# Schemetic.net
KiCad netlist of a schematic drawn in Altium Designer
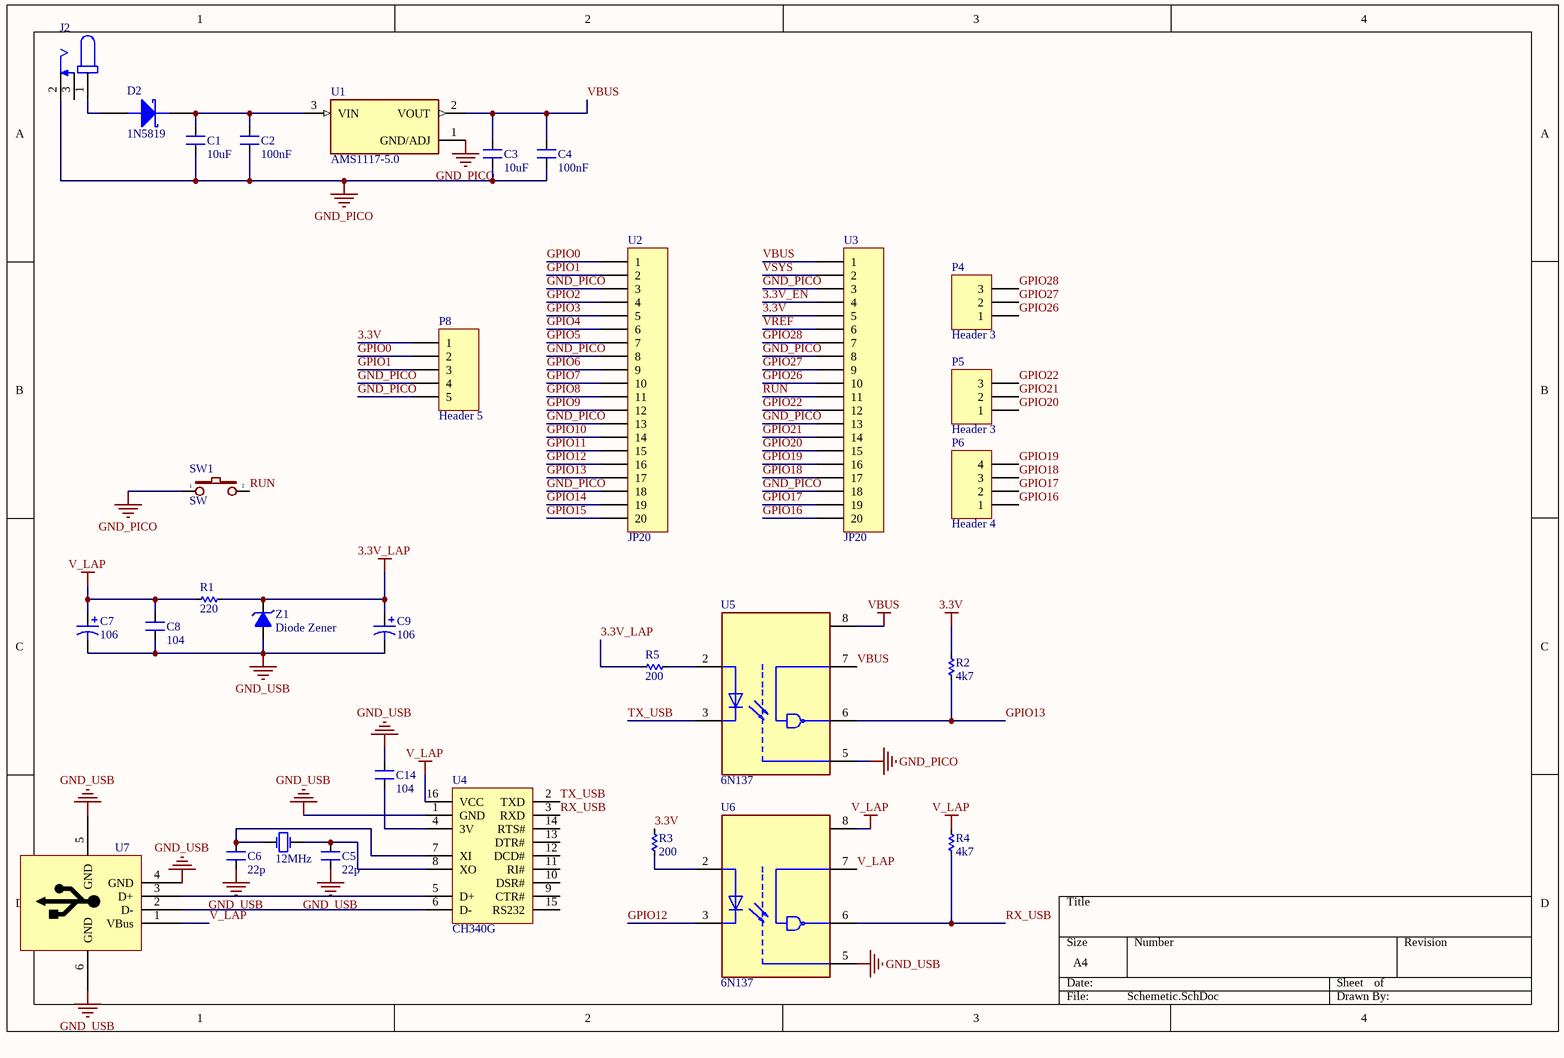
[diagram p0: Schemetic.SchDoc]

(export (version "E")
  (design (tool "Eeschema 10.0.6"))
  (components
    (comp (ref "C1")
      (value "10uF")
      (footprint "CN2")
      (description "Cap np 104 => 105pF")
      (libsource (lib "Altium Library") (part "CN2"))
    )
    (comp (ref "C2")
      (value "100nF")
      (footprint "CN2")
      (description "Cap np 104 => 105pF")
      (libsource (lib "syhaunguyen") (part "CN2"))
    )
    (comp (ref "C3")
      (value "10uF")
      (footprint "CN2")
      (description "Cap np 104 => 105pF")
      (libsource (lib "syhaunguyen") (part "CN2"))
    )
    (comp (ref "C4")
      (value "100nF")
      (footprint "CN2")
      (description "Cap np 104 => 105pF")
      (libsource (lib "syhaunguyen") (part "CN2"))
    )
    (comp (ref "C5")
      (value "22p")
      (footprint "CN2")
      (description "Cap np 104 => 105pF")
      (libsource (lib "syhaunguyen") (part "CN2"))
    )
    (comp (ref "C6")
      (value "22p")
      (footprint "CN2")
      (description "Cap np 104 => 105pF")
      (libsource (lib "syhaunguyen") (part "CN2"))
    )
    (comp (ref "C7")
      (value "106")
      (footprint "C3MM")
      (description "Polarized Capacitor (Axial)")
      (fields (field (name "PUBLISHER") "Altium Limited"))
      (libsource (lib "Schematic") (part "Cap Pol 3mm"))
    )
    (comp (ref "C8")
      (value "104")
      (footprint "CN2")
      (description "Cap np 104 => 105pF")
      (libsource (lib "syhaunguyen") (part "CN2"))
    )
    (comp (ref "C9")
      (value "106")
      (footprint "C3MM")
      (description "Polarized Capacitor (Axial)")
      (fields (field (name "PUBLISHER") "Altium Limited"))
      (libsource (lib "Schematic") (part "Cap Pol 3mm"))
    )
    (comp (ref "C14")
      (value "104")
      (footprint "CN2")
      (description "Cap np 104 => 105pF")
      (libsource (lib "syhaunguyen") (part "CN2"))
    )
    (comp (ref "D2")
      (value "1N5819")
      (footprint "DIODE/POW/1A")
      (description "Schottky Diode")
      (libsource (lib "Cty1") (part "DIODE SCHOTTKY"))
    )
    (comp (ref "J2")
      (value "~")
      (footprint "GCT_DCJ200-10-A-XX-K_REVA")
      (description "Power Barrel Connector Jack 2.05mm ID (0.081), 5.50mm OD (0.217) Through Hole, Right Angle")
      (fields (field (name "MF") "Global Connector Technology") (field (name "MP") "DCJ200-10-A-K1-K"))
      (libsource (lib "DCJ200-10-A-XX-K_REVA") (part "DCJ200-10-A-XX-K_REVA"))
    )
    (comp (ref "P4")
      (value "Header 3")
      (footprint "HDR1X3")
      (description "Header, 3-Pin")
      (fields (field (name "PUBLISHER") "Altium Limited"))
      (libsource (lib "Schematic") (part "Header 3"))
    )
    (comp (ref "P5")
      (value "Header 3")
      (footprint "HDR1X3")
      (description "Header, 3-Pin")
      (fields (field (name "PUBLISHER") "Altium Limited"))
      (libsource (lib "Schematic") (part "Header 3"))
    )
    (comp (ref "P6")
      (value "Header 4")
      (footprint "HDR1X4")
      (description "Header, 4-Pin")
      (fields (field (name "PUBLISHER") "Altium Limited"))
      (libsource (lib "Schematic") (part "Header 4"))
    )
    (comp (ref "P8")
      (value "Header 5")
      (footprint "HDR1X5")
      (description "Header, 5-Pin")
      (fields (field (name "PUBLISHER") "Altium Limited"))
      (libsource (lib "Miscellaneous Connectors") (part "Header 5"))
    )
    (comp (ref "R1")
      (value "220")
      (footprint "RES-1/8W-SMALL-2")
      (description "Res")
      (fields
        (field (name "MANUFACTURER") "Generic Components")
        (field (name "PUBLISHER") "Altium Hobart Technology Centre")
      )
      (libsource (lib "Altium Library") (part "Res"))
    )
    (comp (ref "R2")
      (value "4k7")
      (footprint "RES-1/8W-SMALL-2")
      (description "Res")
      (fields
        (field (name "MANUFACTURER") "Generic Components")
        (field (name "PUBLISHER") "Altium Hobart Technology Centre")
      )
      (libsource (lib "Altium Library") (part "Res"))
    )
    (comp (ref "R3")
      (value "200")
      (footprint "RES-1/8W-SMALL-2")
      (description "Res")
      (fields
        (field (name "MANUFACTURER") "Generic Components")
        (field (name "PUBLISHER") "Altium Hobart Technology Centre")
      )
      (libsource (lib "Altium Library") (part "Res"))
    )
    (comp (ref "R4")
      (value "4k7")
      (footprint "RES-1/8W-SMALL-2")
      (description "Res")
      (fields
        (field (name "MANUFACTURER") "Generic Components")
        (field (name "PUBLISHER") "Altium Hobart Technology Centre")
      )
      (libsource (lib "Altium Library") (part "Res"))
    )
    (comp (ref "R5")
      (value "200")
      (footprint "RES-1/8W-SMALL-2")
      (description "Res")
      (fields
        (field (name "MANUFACTURER") "Generic Components")
        (field (name "PUBLISHER") "Altium Hobart Technology Centre")
      )
      (libsource (lib "Altium Library") (part "Res"))
    )
    (comp (ref "SW1")
      (value "SW")
      (footprint "SW2")
      (description "Switch button 2 pin")
      (libsource (lib "syhaunguyen") (part "SW2"))
    )
    (comp (ref "U1")
      (value "AMS1117-5.0")
      (footprint "SOT229P700X180-4N")
      (description "1A LOW DROPOUT VOLTAGE REGULATOR")
      (fields (field (name "MF") "ams"))
      (libsource (lib "AMS1117-5.0") (part "AMS1117-5.0"))
    )
    (comp (ref "U2")
      (value "JP20")
      (footprint "JP20-C1T")
      (description "WR-PHD 2.54 mm Angled Socket Header")
      (fields
        (field (name "MANUFACTURER") "Würth Elektronik eiSos GmbH")
        (field (name "PARTNO") "613020143121")
        (field (name "CREATED BY") "Karrer Zheng")
      )
      (libsource (lib "Altium Library") (part "JP20"))
    )
    (comp (ref "U3")
      (value "JP20")
      (footprint "JP20-C1T")
      (description "WR-PHD 2.54 mm Angled Socket Header")
      (fields
        (field (name "MANUFACTURER") "Würth Elektronik eiSos GmbH")
        (field (name "PARTNO") "613020143121")
        (field (name "CREATED BY") "Karrer Zheng")
      )
      (libsource (lib "Altium Library") (part "JP20"))
    )
    (comp (ref "U4")
      (value "CH340G")
      (footprint "SO16")
      (description "High and Low Side Driver")
      (fields (field (name "PUBLISHER") "Altium Limited"))
      (libsource (lib "Altium Library") (part "CH340G"))
    )
    (comp (ref "U5")
      (value "6N137")
      (footprint "DIP762W50P254L977H451Q8")
      (description "Logic Output Optoisolator 10Mbps Open Collector 5000Vrms 1 Channel 5kV/Âµs CMTI 8-DIP")
      (fields (field (name "MF") "Everlight Electronics"))
      (libsource (lib "6N137") (part "6N137"))
    )
    (comp (ref "U6")
      (value "6N137")
      (footprint "DIP762W50P254L977H451Q8")
      (description "Logic Output Optoisolator 10Mbps Open Collector 5000Vrms 1 Channel 5kV/Âµs CMTI 8-DIP")
      (fields (field (name "MF") "Everlight Electronics"))
      (libsource (lib "6N137") (part "6N137"))
    )
    (comp (ref "U7")
      (value "USB-A Through-Hole")
      (footprint "USB-A")
      (libsource (lib "Cty1") (part "USB-A TH"))
    )
    (comp (ref "Y1")
      (value "12MHz")
      (footprint "XT2")
      (description "Crystal Oscillator")
      (fields (field (name "PUBLISHER") "Altium Limited"))
      (libsource (lib "Cty1") (part "Crystal"))
    )
    (comp (ref "Z1")
      (value "Diode Zener")
      (footprint "D1A")
      (description "Diode  Zener")
      (libsource (lib "Cty1") (part "Diode Zener"))
    )
  )
  (nets
    (net (code "1") (name "/3.3V_EN") (class "Default")
      (node (ref "U3") (pin "4") (pinfunction "4_4") (pintype "passive"))
    )
    (net (code "2") (name "/GPIO0") (class "Default")
      (node (ref "P8") (pin "2") (pinfunction "2_2") (pintype "passive"))
      (node (ref "U2") (pin "1") (pinfunction "1_1") (pintype "passive"))
    )
    (net (code "3") (name "/GPIO1") (class "Default")
      (node (ref "P8") (pin "3") (pinfunction "3_3") (pintype "passive"))
      (node (ref "U2") (pin "2") (pinfunction "2_2") (pintype "passive"))
    )
    (net (code "4") (name "/GPIO2") (class "Default")
      (node (ref "U2") (pin "4") (pinfunction "4_4") (pintype "passive"))
    )
    (net (code "5") (name "/GPIO3") (class "Default")
      (node (ref "U2") (pin "5") (pinfunction "5_5") (pintype "passive"))
    )
    (net (code "6") (name "/GPIO4") (class "Default")
      (node (ref "U2") (pin "6") (pinfunction "6_6") (pintype "passive"))
    )
    (net (code "7") (name "/GPIO5") (class "Default")
      (node (ref "U2") (pin "7") (pinfunction "7_7") (pintype "passive"))
    )
    (net (code "8") (name "/GPIO6") (class "Default")
      (node (ref "U2") (pin "9") (pinfunction "9_9") (pintype "passive"))
    )
    (net (code "9") (name "/GPIO7") (class "Default")
      (node (ref "U2") (pin "10") (pinfunction "10_10") (pintype "passive"))
    )
    (net (code "10") (name "/GPIO8") (class "Default")
      (node (ref "U2") (pin "11") (pinfunction "11_11") (pintype "passive"))
    )
    (net (code "11") (name "/GPIO9") (class "Default")
      (node (ref "U2") (pin "12") (pinfunction "12_12") (pintype "passive"))
    )
    (net (code "12") (name "/GPIO10") (class "Default")
      (node (ref "U2") (pin "14") (pinfunction "14_14") (pintype "passive"))
    )
    (net (code "13") (name "/GPIO11") (class "Default")
      (node (ref "U2") (pin "15") (pinfunction "15_15") (pintype "passive"))
    )
    (net (code "14") (name "/GPIO12") (class "Default")
      (node (ref "U2") (pin "16") (pinfunction "16_16") (pintype "passive"))
      (node (ref "U6") (pin "3") (pinfunction "C_3") (pintype "passive"))
    )
    (net (code "15") (name "/GPIO13") (class "Default")
      (node (ref "R2") (pin "2") (pinfunction "2_2") (pintype "passive"))
      (node (ref "U2") (pin "17") (pinfunction "17_17") (pintype "passive"))
      (node (ref "U5") (pin "6") (pinfunction "VO_6") (pintype "passive"))
    )
    (net (code "16") (name "/GPIO14") (class "Default")
      (node (ref "U2") (pin "19") (pinfunction "19_19") (pintype "passive"))
    )
    (net (code "17") (name "/GPIO15") (class "Default")
      (node (ref "U2") (pin "20") (pinfunction "20_20") (pintype "passive"))
    )
    (net (code "18") (name "/GPIO16") (class "Default")
      (node (ref "P6") (pin "1") (pinfunction "1_1") (pintype "passive"))
      (node (ref "U3") (pin "20") (pinfunction "20_20") (pintype "passive"))
    )
    (net (code "19") (name "/GPIO17") (class "Default")
      (node (ref "P6") (pin "2") (pinfunction "2_2") (pintype "passive"))
      (node (ref "U3") (pin "19") (pinfunction "19_19") (pintype "passive"))
    )
    (net (code "20") (name "/GPIO18") (class "Default")
      (node (ref "P6") (pin "3") (pinfunction "3_3") (pintype "passive"))
      (node (ref "U3") (pin "17") (pinfunction "17_17") (pintype "passive"))
    )
    (net (code "21") (name "/GPIO19") (class "Default")
      (node (ref "P6") (pin "4") (pinfunction "4_4") (pintype "passive"))
      (node (ref "U3") (pin "16") (pinfunction "16_16") (pintype "passive"))
    )
    (net (code "22") (name "/GPIO20") (class "Default")
      (node (ref "P5") (pin "1") (pinfunction "1_1") (pintype "passive"))
      (node (ref "U3") (pin "15") (pinfunction "15_15") (pintype "passive"))
    )
    (net (code "23") (name "/GPIO21") (class "Default")
      (node (ref "P5") (pin "2") (pinfunction "2_2") (pintype "passive"))
      (node (ref "U3") (pin "14") (pinfunction "14_14") (pintype "passive"))
    )
    (net (code "24") (name "/GPIO22") (class "Default")
      (node (ref "P5") (pin "3") (pinfunction "3_3") (pintype "passive"))
      (node (ref "U3") (pin "12") (pinfunction "12_12") (pintype "passive"))
    )
    (net (code "25") (name "/GPIO26") (class "Default")
      (node (ref "P4") (pin "1") (pinfunction "1_1") (pintype "passive"))
      (node (ref "U3") (pin "10") (pinfunction "10_10") (pintype "passive"))
    )
    (net (code "26") (name "/GPIO27") (class "Default")
      (node (ref "P4") (pin "2") (pinfunction "2_2") (pintype "passive"))
      (node (ref "U3") (pin "9") (pinfunction "9_9") (pintype "passive"))
    )
    (net (code "27") (name "/GPIO28") (class "Default")
      (node (ref "P4") (pin "3") (pinfunction "3_3") (pintype "passive"))
      (node (ref "U3") (pin "7") (pinfunction "7_7") (pintype "passive"))
    )
    (net (code "28") (name "/RUN") (class "Default")
      (node (ref "SW1") (pin "2") (pinfunction "2_2") (pintype "passive"))
      (node (ref "U3") (pin "11") (pinfunction "11_11") (pintype "passive"))
    )
    (net (code "29") (name "/RX_USB") (class "Default")
      (node (ref "R4") (pin "2") (pinfunction "2_2") (pintype "passive"))
      (node (ref "U4") (pin "3") (pinfunction "RXD_3") (pintype "passive"))
      (node (ref "U6") (pin "6") (pinfunction "VO_6") (pintype "passive"))
    )
    (net (code "30") (name "/TX_USB") (class "Default")
      (node (ref "U4") (pin "2") (pinfunction "TXD_2") (pintype "passive"))
      (node (ref "U5") (pin "3") (pinfunction "C_3") (pintype "passive"))
    )
    (net (code "31") (name "/VREF") (class "Default")
      (node (ref "U3") (pin "6") (pinfunction "6_6") (pintype "passive"))
    )
    (net (code "32") (name "/VSYS") (class "Default")
      (node (ref "U3") (pin "2") (pinfunction "2_2") (pintype "passive"))
    )
    (net (code "33") (name "3.3V") (class "Default")
      (node (ref "P8") (pin "1") (pinfunction "1_1") (pintype "passive"))
      (node (ref "R2") (pin "1") (pinfunction "1_1") (pintype "passive"))
      (node (ref "R3") (pin "1") (pinfunction "1_1") (pintype "passive"))
      (node (ref "U3") (pin "5") (pinfunction "5_5") (pintype "passive"))
    )
    (net (code "34") (name "3.3V_LAP") (class "Default")
      (node (ref "C9") (pin "1") (pinfunction "1_1") (pintype "passive"))
      (node (ref "R1") (pin "1") (pinfunction "1_1") (pintype "passive"))
      (node (ref "R5") (pin "1") (pinfunction "1_1") (pintype "passive"))
      (node (ref "Z1") (pin "2") (pinfunction "K_2") (pintype "passive"))
    )
    (net (code "35") (name "GND_PICO") (class "Default")
      (node (ref "C1") (pin "1") (pinfunction "1_1") (pintype "passive"))
      (node (ref "C2") (pin "1") (pinfunction "1_1") (pintype "passive"))
      (node (ref "C3") (pin "1") (pinfunction "1_1") (pintype "passive"))
      (node (ref "C4") (pin "1") (pinfunction "1_1") (pintype "passive"))
      (node (ref "J2") (pin "2") (pinfunction "2_2") (pintype "passive"))
      (node (ref "P8") (pin "4") (pinfunction "4_4") (pintype "passive"))
      (node (ref "P8") (pin "5") (pinfunction "5_5") (pintype "passive"))
      (node (ref "SW1") (pin "1") (pinfunction "1_1") (pintype "passive"))
      (node (ref "U1") (pin "1") (pinfunction "GND/ADJ_1") (pintype "power_in"))
      (node (ref "U2") (pin "13") (pinfunction "13_13") (pintype "passive"))
      (node (ref "U2") (pin "18") (pinfunction "18_18") (pintype "passive"))
      (node (ref "U2") (pin "3") (pinfunction "3_3") (pintype "passive"))
      (node (ref "U2") (pin "8") (pinfunction "8_8") (pintype "passive"))
      (node (ref "U3") (pin "13") (pinfunction "13_13") (pintype "passive"))
      (node (ref "U3") (pin "18") (pinfunction "18_18") (pintype "passive"))
      (node (ref "U3") (pin "3") (pinfunction "3_3") (pintype "passive"))
      (node (ref "U3") (pin "8") (pinfunction "8_8") (pintype "passive"))
      (node (ref "U5") (pin "5") (pinfunction "GND_5") (pintype "power_in"))
    )
    (net (code "36") (name "GND_USB") (class "Default")
      (node (ref "C14") (pin "1") (pinfunction "1_1") (pintype "passive"))
      (node (ref "C5") (pin "1") (pinfunction "1_1") (pintype "passive"))
      (node (ref "C6") (pin "1") (pinfunction "1_1") (pintype "passive"))
      (node (ref "C7") (pin "2") (pinfunction "2_2") (pintype "passive"))
      (node (ref "C8") (pin "1") (pinfunction "1_1") (pintype "passive"))
      (node (ref "C9") (pin "2") (pinfunction "2_2") (pintype "passive"))
      (node (ref "U4") (pin "1") (pinfunction "GND_1") (pintype "passive"))
      (node (ref "U6") (pin "5") (pinfunction "GND_5") (pintype "power_in"))
      (node (ref "U7") (pin "4") (pinfunction "GND_4") (pintype "passive"))
      (node (ref "U7") (pin "5") (pinfunction "GND_5") (pintype "passive"))
      (node (ref "U7") (pin "6") (pinfunction "GND_6") (pintype "passive"))
      (node (ref "Z1") (pin "1") (pinfunction "A_1") (pintype "passive"))
    )
    (net (code "37") (name "Net-(D2-A)") (class "Default")
      (node (ref "D2") (pin "1") (pinfunction "A_1") (pintype "passive"))
      (node (ref "J2") (pin "1") (pinfunction "1_1") (pintype "passive"))
    )
    (net (code "38") (name "Net-(D2-K)") (class "Default")
      (node (ref "C1") (pin "2") (pinfunction "2_2") (pintype "passive"))
      (node (ref "C2") (pin "2") (pinfunction "2_2") (pintype "passive"))
      (node (ref "D2") (pin "2") (pinfunction "K_2") (pintype "passive"))
      (node (ref "U1") (pin "3") (pinfunction "VIN_3") (pintype "input"))
    )
    (net (code "39") (name "Net-(U4-3V)") (class "Default")
      (node (ref "C14") (pin "2") (pinfunction "2_2") (pintype "passive"))
      (node (ref "U4") (pin "4") (pinfunction "3V_4") (pintype "passive"))
    )
    (net (code "40") (name "Net-(U4-D+)") (class "Default")
      (node (ref "U4") (pin "5") (pinfunction "D+_5") (pintype "passive"))
      (node (ref "U7") (pin "3") (pinfunction "D+_3") (pintype "passive"))
    )
    (net (code "41") (name "Net-(U4-D-)") (class "Default")
      (node (ref "U4") (pin "6") (pinfunction "D-_6") (pintype "passive"))
      (node (ref "U7") (pin "2") (pinfunction "D-_2") (pintype "passive"))
    )
    (net (code "42") (name "Net-(U4-XI)") (class "Default")
      (node (ref "C6") (pin "2") (pinfunction "2_2") (pintype "passive"))
      (node (ref "U4") (pin "7") (pinfunction "XI_7") (pintype "passive"))
      (node (ref "Y1") (pin "2") (pinfunction "OSC2_2") (pintype "passive"))
    )
    (net (code "43") (name "Net-(U4-XO)") (class "Default")
      (node (ref "C5") (pin "2") (pinfunction "2_2") (pintype "passive"))
      (node (ref "U4") (pin "8") (pinfunction "XO_8") (pintype "passive"))
      (node (ref "Y1") (pin "1") (pinfunction "OSC1_1") (pintype "passive"))
    )
    (net (code "44") (name "Net-(U5-A)") (class "Default")
      (node (ref "R5") (pin "2") (pinfunction "2_2") (pintype "passive"))
      (node (ref "U5") (pin "2") (pinfunction "A_2") (pintype "passive"))
    )
    (net (code "45") (name "Net-(U6-A)") (class "Default")
      (node (ref "R3") (pin "2") (pinfunction "2_2") (pintype "passive"))
      (node (ref "U6") (pin "2") (pinfunction "A_2") (pintype "passive"))
    )
    (net (code "46") (name "VBUS") (class "Default")
      (node (ref "C3") (pin "2") (pinfunction "2_2") (pintype "passive"))
      (node (ref "C4") (pin "2") (pinfunction "2_2") (pintype "passive"))
      (node (ref "U1") (pin "2") (pinfunction "VOUT_2") (pintype "output"))
      (node (ref "U3") (pin "1") (pinfunction "1_1") (pintype "passive"))
      (node (ref "U5") (pin "7") (pinfunction "VE_7") (pintype "passive"))
      (node (ref "U5") (pin "8") (pinfunction "VCC_8") (pintype "passive"))
    )
    (net (code "47") (name "V_LAP") (class "Default")
      (node (ref "C7") (pin "1") (pinfunction "1_1") (pintype "passive"))
      (node (ref "C8") (pin "2") (pinfunction "2_2") (pintype "passive"))
      (node (ref "R1") (pin "2") (pinfunction "2_2") (pintype "passive"))
      (node (ref "R4") (pin "1") (pinfunction "1_1") (pintype "passive"))
      (node (ref "U4") (pin "16") (pinfunction "VCC_16") (pintype "passive"))
      (node (ref "U6") (pin "7") (pinfunction "VE_7") (pintype "passive"))
      (node (ref "U6") (pin "8") (pinfunction "VCC_8") (pintype "passive"))
      (node (ref "U7") (pin "1") (pinfunction "VBus_1") (pintype "passive"))
    )
    (net (code "48") (name "unconnected-(J2-Pad3)") (class "Default")
      (node (ref "J2") (pin "3") (pinfunction "3_3") (pintype "passive"))
    )
    (net (code "49") (name "unconnected-(U4-CTR#-Pad9)") (class "Default")
      (node (ref "U4") (pin "9") (pinfunction "CTR#_9") (pintype "passive"))
    )
    (net (code "50") (name "unconnected-(U4-DCD#-Pad12)") (class "Default")
      (node (ref "U4") (pin "12") (pinfunction "DCD#_12") (pintype "passive"))
    )
    (net (code "51") (name "unconnected-(U4-DSR#-Pad10)") (class "Default")
      (node (ref "U4") (pin "10") (pinfunction "DSR#_10") (pintype "passive"))
    )
    (net (code "52") (name "unconnected-(U4-DTR#-Pad13)") (class "Default")
      (node (ref "U4") (pin "13") (pinfunction "DTR#_13") (pintype "passive"))
    )
    (net (code "53") (name "unconnected-(U4-RI#-Pad11)") (class "Default")
      (node (ref "U4") (pin "11") (pinfunction "RI#_11") (pintype "passive"))
    )
    (net (code "54") (name "unconnected-(U4-RS232-Pad15)") (class "Default")
      (node (ref "U4") (pin "15") (pinfunction "RS232_15") (pintype "passive"))
    )
    (net (code "55") (name "unconnected-(U4-RTS#-Pad14)") (class "Default")
      (node (ref "U4") (pin "14") (pinfunction "RTS#_14") (pintype "passive"))
    )
  )
)
